# VREF.net
KiCad netlist of a schematic drawn in Altium Designer
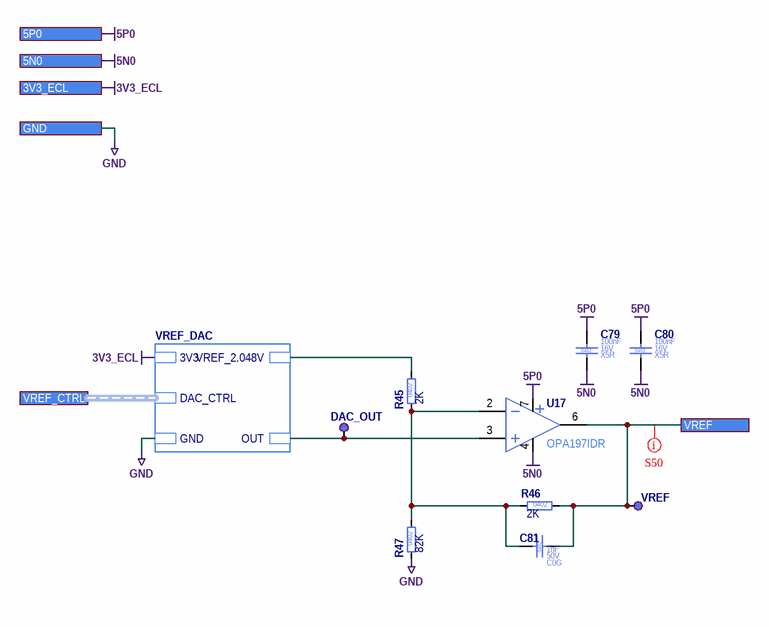
[diagram p0: VREF.SchDoc]

(export (version "E")
  (design (tool "Eeschema 10.0.6"))
  (components
    (comp (ref "C79")
      (value "C_100NF_16V_X5R_0402_10")
      (footprint "C_0402_1005")
      (description "Ceramic Capacitor")
      (fields
        (field (name "CASE/PACKAGE") "0402")
        (field (name "VOLTAGE RATING (DC)") "16V")
        (field (name "DIELECTRIC") "X5R")
        (field (name "CAPACITANCE") "100nF")
        (field (name "TOLERANCE") "10%")
        (field (name "MANUFACTURER PART NUMBER") "EMK105BJ104KV-F")
      )
      (libsource (lib "7Sigma") (part "C"))
    )
    (comp (ref "C80")
      (value "C_100NF_16V_X5R_0402_10")
      (footprint "C_0402_1005")
      (description "Ceramic Capacitor")
      (fields
        (field (name "CASE/PACKAGE") "0402")
        (field (name "VOLTAGE RATING (DC)") "16V")
        (field (name "DIELECTRIC") "X5R")
        (field (name "CAPACITANCE") "100nF")
        (field (name "TOLERANCE") "10%")
        (field (name "MANUFACTURER PART NUMBER") "EMK105BJ104KV-F")
      )
      (libsource (lib "7Sigma") (part "C"))
    )
    (comp (ref "C81")
      (value "C_1NF_50V_C0G_0402_5")
      (footprint "C_0402_1005")
      (description "Ceramic Capacitor")
      (fields
        (field (name "CASE/PACKAGE") "0402")
        (field (name "VOLTAGE RATING (DC)") "50V")
        (field (name "DIELECTRIC") "C0G")
        (field (name "CAPACITANCE") "1nF")
        (field (name "TOLERANCE") "5%")
        (field (name "MANUFACTURER PART NUMBER") "UMK105CG102JV-F")
      )
      (libsource (lib "7Sigma") (part "C"))
    )
    (comp (ref "DAC_OUT")
      (value "TP_PAD_1.3MM")
      (footprint "TP_PAD_1.3MM")
      (description "Testpoint SMD 1.3mm")
      (libsource (lib "7Sigma") (part "TESTPOINT"))
    )
    (comp (ref "R45")
      (value "R_2K_0402_1")
      (footprint "R_0402_1005")
      (description "Thick Film Resistor")
      (fields
        (field (name "RESISTANCE") "2K")
        (field (name "CASE/PACKAGE") "0402")
        (field (name "TOLERANCE") "1%")
        (field (name "MANUFACTURER") "Yageo")
      )
      (libsource (lib "7Sigma") (part "R"))
    )
    (comp (ref "R46")
      (value "R_2K_0402_1")
      (footprint "R_0402_1005")
      (description "Thick Film Resistor")
      (fields
        (field (name "RESISTANCE") "2K")
        (field (name "CASE/PACKAGE") "0402")
        (field (name "TOLERANCE") "1%")
        (field (name "MANUFACTURER") "Yageo")
      )
      (libsource (lib "7Sigma") (part "R"))
    )
    (comp (ref "R47")
      (value "R_82K_0402_1")
      (footprint "R_0402_1005")
      (description "Thisk Film Resistor")
      (fields
        (field (name "RESISTANCE") "82K")
        (field (name "CASE/PACKAGE") "0402")
        (field (name "TOLERANCE") "1%")
        (field (name "MANUFACTURER") "Yageo")
      )
      (libsource (lib "7Sigma") (part "R"))
    )
    (comp (ref "U17")
      (value "OPA197IDR")
      (footprint "SOIC127P600X170-8N")
      (description "Single Precision Rail-to-Rail Input Outpu Low Offset Voltage Op Amp")
      (fields
        (field (name "MANUFACTURER PART NUMBER") "OPA197IDR")
        (field (name "MANUFACTURER") "Texas Instruments")
      )
      (libsource (lib "7Sigma") (part "OPA197"))
    )
    (comp (ref "VREF")
      (value "TP_PAD_1.3MM")
      (footprint "TP_PAD_1.3MM")
      (description "Testpoint SMD 1.3mm")
      (libsource (lib "7Sigma") (part "TESTPOINT"))
    )
  )
  (nets
    (net (code "2") (name "/OUT") (class "Default")
      (node (ref "DAC_OUT") (pin "1") (pinfunction "TP_1") (pintype "passive"))
      (node (ref "U17") (pin "3") (pinfunction "INA+_3") (pintype "passive"))
    )
    (net (code "3") (name "/VREF") (class "Default")
      (node (ref "C81") (pin "2") (pinfunction "2_2") (pintype "passive"))
      (node (ref "R46") (pin "2") (pinfunction "2_2") (pintype "passive"))
      (node (ref "U17") (pin "6") (pinfunction "OUTA_6") (pintype "passive"))
      (node (ref "VREF") (pin "1") (pinfunction "TP_1") (pintype "passive"))
    )
    (net (code "4") (name "/VREF_2.048V") (class "Default")
      (node (ref "R45") (pin "2") (pinfunction "2_2") (pintype "passive"))
    )
    (net (code "7") (name "5N0") (class "Default")
      (node (ref "C79") (pin "2") (pinfunction "2_2") (pintype "passive"))
      (node (ref "C80") (pin "2") (pinfunction "2_2") (pintype "passive"))
      (node (ref "U17") (pin "4") (pinfunction "VSS_4") (pintype "power_in"))
    )
    (net (code "8") (name "5P0") (class "Default")
      (node (ref "C79") (pin "1") (pinfunction "1_1") (pintype "passive"))
      (node (ref "C80") (pin "1") (pinfunction "1_1") (pintype "passive"))
      (node (ref "U17") (pin "7") (pinfunction "VDD_7") (pintype "power_in"))
    )
    (net (code "9") (name "GND") (class "Default")
      (node (ref "R47") (pin "1") (pinfunction "1_1") (pintype "passive"))
    )
    (net (code "10") (name "Net-(U17-INA-)") (class "Default")
      (node (ref "C81") (pin "1") (pinfunction "1_1") (pintype "passive"))
      (node (ref "R45") (pin "1") (pinfunction "1_1") (pintype "passive"))
      (node (ref "R46") (pin "1") (pinfunction "1_1") (pintype "passive"))
      (node (ref "R47") (pin "2") (pinfunction "2_2") (pintype "passive"))
      (node (ref "U17") (pin "2") (pinfunction "INA-_2") (pintype "passive"))
    )
    (net (code "11") (name "unconnected-(U17-NC-Pad1)") (class "Default")
      (node (ref "U17") (pin "1") (pinfunction "NC_1") (pintype "passive"))
    )
    (net (code "12") (name "unconnected-(U17-NC-Pad5)") (class "Default")
      (node (ref "U17") (pin "5") (pinfunction "NC_5") (pintype "passive"))
    )
    (net (code "13") (name "unconnected-(U17-NC-Pad8)") (class "Default")
      (node (ref "U17") (pin "8") (pinfunction "NC_8") (pintype "passive"))
    )
  )
)
